# LM2587.net
KiCad netlist of a schematic drawn in Altium Designer
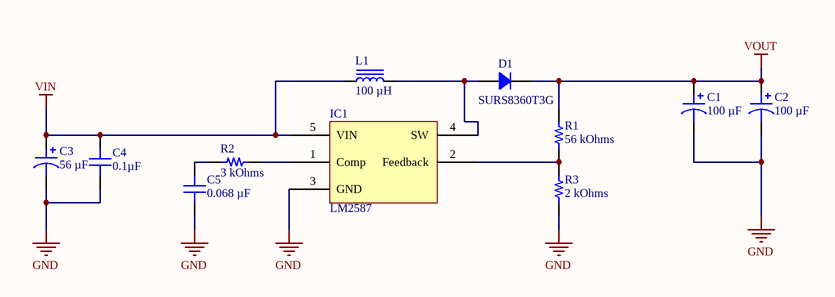
[diagram p0: LM2587.SchDoc]

(export (version "E")
  (design (tool "Eeschema 10.0.6"))
  (components
    (comp (ref "C1")
      (value "100 µF")
      (footprint "CAP ALSMD 8.3MM H10.5MM")
      (description "CAP ALUM 100UF 20% 50V SMD")
      (fields (field (name "PART NUMBER") "50SEV100M8X10.5") (field (name "MANUFACTURER") "Rubycon"))
      (libsource (lib "Celestial Altium Library - altium_library (1)") (part "Polarised Capacitor"))
    )
    (comp (ref "C2")
      (value "100 µF")
      (footprint "CAP ALSMD 8.3MM H10.5MM")
      (description "CAP ALUM 100UF 20% 50V SMD")
      (fields (field (name "PART NUMBER") "50SEV100M8X10.5") (field (name "MANUFACTURER") "Rubycon"))
      (libsource (lib "Celestial Altium Library - altium_library (1)") (part "Polarised Capacitor"))
    )
    (comp (ref "C3")
      (value "56 µF")
      (footprint "CAP ALSMD 6.6MM H7.7MM")
      (description "CAP ALUM 56UF 20% 35V SMD")
      (fields (field (name "PART NUMBER") "865080545010") (field (name "MANUFACTURER") "Würth Elektronik"))
      (libsource (lib "Celestial Altium Library - altium_library (1)") (part "Polarised Capacitor"))
    )
    (comp (ref "C4")
      (value "0.1µF")
      (footprint "CAP 0805_2012")
      (description "CAP CER 0.1UF 35V X7R 0805")
      (fields
        (field (name "PART NUMBER") "0805DC104MAT2A")
        (field (name "CAPACITANCE") "0.1µF")
        (field (name "MANUFACTURER") "AVX Corporation")
      )
      (libsource (lib "Celestial Altium Library - altium_library (1)") (part "Capacitor"))
    )
    (comp (ref "C5")
      (value "0.068 µF")
      (footprint "CAP 0805_2012")
      (description "CAP CER 0.068UF 50V X7R 0805")
      (fields
        (field (name "PART NUMBER") "0805B683K500CT")
        (field (name "CAPACITANCE") "0.068 µF")
        (field (name "MANUFACTURER") "Walsin Technology Corporation")
      )
      (libsource (lib "Celestial Altium Library - altium_library (1)") (part "Capacitor"))
    )
    (comp (ref "D1")
      (value "SURS8360T3G")
      (footprint "DO214AB SMC")
      (description "DIODE GEN PURP 600V 3A SMC")
      (fields (field (name "MANUFACTURER") "ON Semiconductor"))
      (libsource (lib "Celestial Altium Library - altium_library (1)") (part "Diode"))
    )
    (comp (ref "IC1")
      (value "LM2587")
      (footprint "LM2596:D2PAK")
      (description "boost converter")
      (libsource (lib "altiumlive") (part "LM2587"))
    )
    (comp (ref "L1")
      (value "100 µH")
      (footprint "BOURNS SRR1280")
      (description "FIXED IND 100UH 2.1A 150MOHM SMD")
      (fields (field (name "PART NUMBER") "SRR1280-101M") (field (name "MANUFACTURER") "Bourns Inc."))
      (libsource (lib "Celestial Altium Library - altium_library (1)") (part "Inductor"))
    )
    (comp (ref "R1")
      (value "56 kOhms")
      (footprint "RES 0805_2012")
      (description "3430 A2 1% 56K 100PPM 1K RL")
      (fields
        (field (name "PART NUMBER") "3430A2F56KTDF")
        (field (name "MANUFACTURER") "TE Connectivity Passive Product")
      )
      (libsource (lib "Celestial Altium Library - altium_library (1)") (part "Resistor"))
    )
    (comp (ref "R2")
      (value "3 kOhms")
      (footprint "RES 0805_2012")
      (description "3430 A2 1% 3K0 100PPM 1K RL")
      (fields
        (field (name "PART NUMBER") "3430A2F3K0TDF")
        (field (name "MANUFACTURER") "TE Connectivity Passive Product")
      )
      (libsource (lib "Celestial Altium Library - altium_library (1)") (part "Resistor"))
    )
    (comp (ref "R3")
      (value "2 kOhms")
      (footprint "RES 0805_2012")
      (description "3430 A2 1% 2K0 100PPM 1K RL")
      (fields
        (field (name "PART NUMBER") "3430A2F2K0TDF")
        (field (name "MANUFACTURER") "TE Connectivity Passive Product")
      )
      (libsource (lib "Celestial Altium Library - altium_library (1)") (part "Resistor"))
    )
  )
  (nets
    (net (code "1") (name "GND") (class "Default")
      (node (ref "C1") (pin "2") (pinfunction "2_2") (pintype "passive"))
      (node (ref "C2") (pin "2") (pinfunction "2_2") (pintype "passive"))
      (node (ref "C3") (pin "2") (pinfunction "2_2") (pintype "passive"))
      (node (ref "C4") (pin "1") (pinfunction "1_1") (pintype "passive"))
      (node (ref "C5") (pin "1") (pinfunction "1_1") (pintype "passive"))
      (node (ref "IC1") (pin "3") (pinfunction "GND_3") (pintype "passive"))
      (node (ref "R3") (pin "1") (pinfunction "1_1") (pintype "passive"))
    )
    (net (code "2") (name "Net-(C5-Pad2)") (class "Default")
      (node (ref "C5") (pin "2") (pinfunction "2_2") (pintype "passive"))
      (node (ref "R2") (pin "1") (pinfunction "1_1") (pintype "passive"))
    )
    (net (code "3") (name "Net-(IC1-Comp)") (class "Default")
      (node (ref "IC1") (pin "1") (pinfunction "Comp_1") (pintype "passive"))
      (node (ref "R2") (pin "2") (pinfunction "2_2") (pintype "passive"))
    )
    (net (code "4") (name "Net-(IC1-Feedback)") (class "Default")
      (node (ref "IC1") (pin "2") (pinfunction "Feedback_2") (pintype "passive"))
      (node (ref "R1") (pin "1") (pinfunction "1_1") (pintype "passive"))
      (node (ref "R3") (pin "2") (pinfunction "2_2") (pintype "passive"))
    )
    (net (code "5") (name "Net-(IC1-SW)") (class "Default")
      (node (ref "D1") (pin "1") (pinfunction "1_1") (pintype "passive"))
      (node (ref "IC1") (pin "4") (pinfunction "SW_4") (pintype "passive"))
      (node (ref "L1") (pin "2") (pinfunction "2_2") (pintype "passive"))
    )
    (net (code "6") (name "VIN") (class "Default")
      (node (ref "C3") (pin "1") (pinfunction "1_1") (pintype "passive"))
      (node (ref "C4") (pin "2") (pinfunction "2_2") (pintype "passive"))
      (node (ref "IC1") (pin "5") (pinfunction "VIN_5") (pintype "passive"))
      (node (ref "L1") (pin "1") (pinfunction "1_1") (pintype "passive"))
    )
    (net (code "7") (name "VOUT") (class "Default")
      (node (ref "C1") (pin "1") (pinfunction "1_1") (pintype "passive"))
      (node (ref "C2") (pin "1") (pinfunction "1_1") (pintype "passive"))
      (node (ref "D1") (pin "2") (pinfunction "2_2") (pintype "passive"))
      (node (ref "R1") (pin "2") (pinfunction "2_2") (pintype "passive"))
    )
  )
)
